# heater.net
KiCad netlist of a schematic drawn in Altium Designer
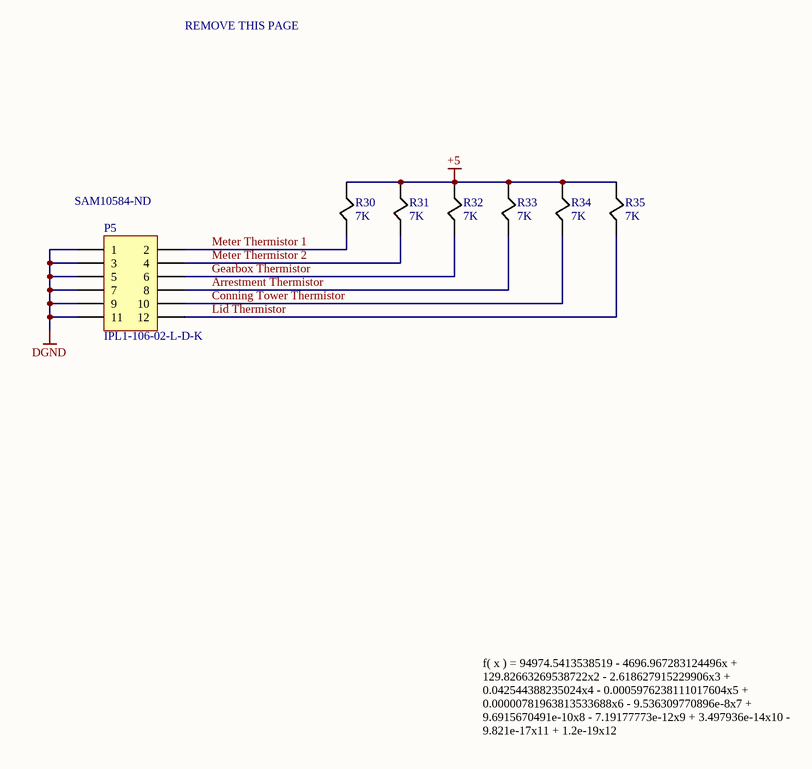
[diagram p0: heater.SchDoc]

(export (version "E")
  (design (tool "Eeschema 10.0.6"))
  (components
    (comp (ref "P5")
      (value "IPL1-106-02-L-D-K")
      (description "CONN SHROUDED PWR HEADER 12POS")
      (fields (field (name "SUPPLIER PART NUMBER 1") "SAM10584-ND"))
      (libsource (lib "Miscellaneous Connectors") (part "Header 6X2"))
    )
    (comp (ref "R30")
      (value "7K")
      (footprint "0805")
      (description "RES SMD 6.98K OHM 1% 1/8W 0805")
      (fields (field (name "TOLERANCE") "±1%"))
      (libsource (lib "*") (part "RES1"))
    )
    (comp (ref "R31")
      (value "7K")
      (footprint "0805")
      (description "RES SMD 6.98K OHM 1% 1/8W 0805")
      (fields (field (name "TOLERANCE") "±1%"))
      (libsource (lib "*") (part "RES1"))
    )
    (comp (ref "R32")
      (value "7K")
      (footprint "0805")
      (description "RES SMD 6.98K OHM 1% 1/8W 0805")
      (fields (field (name "TOLERANCE") "±1%"))
      (libsource (lib "*") (part "RES1"))
    )
    (comp (ref "R33")
      (value "7K")
      (footprint "0805")
      (description "RES SMD 6.98K OHM 1% 1/8W 0805")
      (fields (field (name "TOLERANCE") "±1%"))
      (libsource (lib "*") (part "RES1"))
    )
    (comp (ref "R34")
      (value "7K")
      (footprint "0805")
      (description "RES SMD 6.98K OHM 1% 1/8W 0805")
      (fields (field (name "TOLERANCE") "±1%"))
      (libsource (lib "*") (part "RES1"))
    )
    (comp (ref "R35")
      (value "7K")
      (footprint "0805")
      (description "RES SMD 6.98K OHM 1% 1/8W 0805")
      (fields (field (name "TOLERANCE") "±1%"))
      (libsource (lib "*") (part "RES1"))
    )
  )
  (nets
    (net (code "1") (name "+5") (class "Default")
      (node (ref "R30") (pin "2") (pinfunction "2_2") (pintype "passive"))
      (node (ref "R31") (pin "2") (pinfunction "2_2") (pintype "passive"))
      (node (ref "R32") (pin "2") (pinfunction "2_2") (pintype "passive"))
      (node (ref "R33") (pin "2") (pinfunction "2_2") (pintype "passive"))
      (node (ref "R34") (pin "2") (pinfunction "2_2") (pintype "passive"))
      (node (ref "R35") (pin "2") (pinfunction "2_2") (pintype "passive"))
    )
    (net (code "2") (name "/Arrestment Thermistor") (class "Default")
      (node (ref "P5") (pin "8") (pinfunction "8_8") (pintype "passive"))
      (node (ref "R33") (pin "1") (pinfunction "1_1") (pintype "passive"))
    )
    (net (code "3") (name "/Conning Tower Thermistor") (class "Default")
      (node (ref "P5") (pin "10") (pinfunction "10_10") (pintype "passive"))
      (node (ref "R34") (pin "1") (pinfunction "1_1") (pintype "passive"))
    )
    (net (code "4") (name "/Gearbox Thermistor") (class "Default")
      (node (ref "P5") (pin "6") (pinfunction "6_6") (pintype "passive"))
      (node (ref "R32") (pin "1") (pinfunction "1_1") (pintype "passive"))
    )
    (net (code "5") (name "/Lid Thermistor") (class "Default")
      (node (ref "P5") (pin "12") (pinfunction "12_12") (pintype "passive"))
      (node (ref "R35") (pin "1") (pinfunction "1_1") (pintype "passive"))
    )
    (net (code "6") (name "/Meter Thermistor 1") (class "Default")
      (node (ref "P5") (pin "2") (pinfunction "2_2") (pintype "passive"))
      (node (ref "R30") (pin "1") (pinfunction "1_1") (pintype "passive"))
    )
    (net (code "7") (name "/Meter Thermistor 2") (class "Default")
      (node (ref "P5") (pin "4") (pinfunction "4_4") (pintype "passive"))
      (node (ref "R31") (pin "1") (pinfunction "1_1") (pintype "passive"))
    )
    (net (code "8") (name "DGND") (class "Default")
      (node (ref "P5") (pin "1") (pinfunction "1_1") (pintype "passive"))
      (node (ref "P5") (pin "11") (pinfunction "11_11") (pintype "passive"))
      (node (ref "P5") (pin "3") (pinfunction "3_3") (pintype "passive"))
      (node (ref "P5") (pin "5") (pinfunction "5_5") (pintype "passive"))
      (node (ref "P5") (pin "7") (pinfunction "7_7") (pintype "passive"))
      (node (ref "P5") (pin "9") (pinfunction "9_9") (pintype "passive"))
    )
  )
)
